# encoder.net
KiCad netlist of a schematic drawn in EAGLE
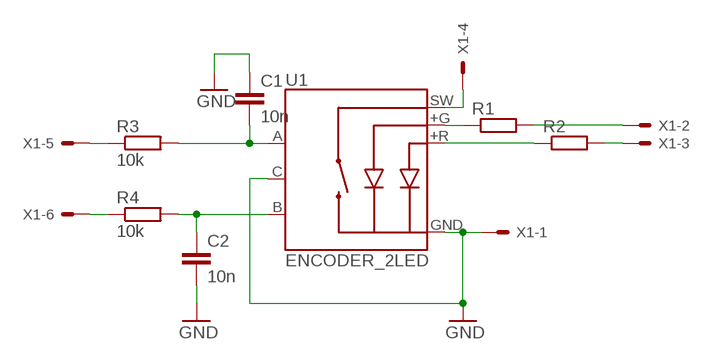
[diagram p0: schematic, sheet 1]

(export (version "E")
  (design (tool "Eeschema 10.0.6"))
  (components
    (comp (ref "C1")
      (value "10n")
      (footprint "eagle-import:C025-024X044")
      (libsource (lib "eagle-import") (part "C-EU025-024X044"))
    )
    (comp (ref "C2")
      (value "10n")
      (footprint "eagle-import:C025-024X044")
      (libsource (lib "eagle-import") (part "C-EU025-024X044"))
    )
    (comp (ref "R1")
      (value "R-EU_R0603")
      (footprint "eagle-import:R0603")
      (libsource (lib "eagle-import") (part "R-EU_R0603"))
    )
    (comp (ref "R2")
      (value "R-EU_R0603")
      (footprint "eagle-import:R0603")
      (libsource (lib "eagle-import") (part "R-EU_R0603"))
    )
    (comp (ref "R3")
      (value "10k")
      (footprint "eagle-import:R0603")
      (libsource (lib "eagle-import") (part "R-EU_R0603"))
    )
    (comp (ref "R4")
      (value "10k")
      (footprint "eagle-import:R0603")
      (libsource (lib "eagle-import") (part "R-EU_R0603"))
    )
    (comp (ref "U1")
      (value "ENCODER_2LED")
      (footprint "eagle-import:ENCODER_LED_2")
      (libsource (lib "eagle-import") (part "ENCODER_2LED"))
    )
    (comp (ref "X1")
      (value "22-23-2061")
      (footprint "eagle-import:22-23-2061")
      (fields (field (name "MF") "MOLEX"))
      (libsource (lib "eagle-import") (part "22-23-2061"))
    )
  )
  (nets
    (net (code "1") (name "GND") (class "Default")
      (node (ref "C1") (pin "1") (pinfunction "1_1") (pintype "passive"))
      (node (ref "C2") (pin "2") (pinfunction "2_2") (pintype "passive"))
      (node (ref "U1") (pin "C") (pinfunction "C_C") (pintype "bidirectional"))
      (node (ref "U1") (pin "GND") (pinfunction "-_GND") (pintype "passive"))
      (node (ref "X1") (pin "1") (pinfunction "S_1") (pintype "passive"))
    )
    (net (code "2") (name "Net-(C1-Pad2)") (class "Default")
      (node (ref "C1") (pin "2") (pinfunction "2_2") (pintype "passive"))
      (node (ref "R3") (pin "2") (pinfunction "2_2") (pintype "passive"))
      (node (ref "U1") (pin "A") (pinfunction "A_A") (pintype "bidirectional"))
    )
    (net (code "3") (name "Net-(C2-Pad1)") (class "Default")
      (node (ref "C2") (pin "1") (pinfunction "1_1") (pintype "passive"))
      (node (ref "R4") (pin "2") (pinfunction "2_2") (pintype "passive"))
      (node (ref "U1") (pin "B") (pinfunction "B_B") (pintype "bidirectional"))
    )
    (net (code "4") (name "Net-(R1-Pad1)") (class "Default")
      (node (ref "R1") (pin "1") (pinfunction "1_1") (pintype "passive"))
      (node (ref "U1") (pin "+G") (pinfunction "+G_+G") (pintype "passive"))
    )
    (net (code "5") (name "Net-(R2-Pad1)") (class "Default")
      (node (ref "R2") (pin "1") (pinfunction "1_1") (pintype "passive"))
      (node (ref "U1") (pin "+R") (pinfunction "+R_+R") (pintype "passive"))
    )
    (net (code "6") (name "Net-(X1B-S)") (class "Default")
      (node (ref "R1") (pin "2") (pinfunction "2_2") (pintype "passive"))
      (node (ref "X1") (pin "2") (pinfunction "S_2") (pintype "passive"))
    )
    (net (code "7") (name "Net-(X1C-S)") (class "Default")
      (node (ref "R2") (pin "2") (pinfunction "2_2") (pintype "passive"))
      (node (ref "X1") (pin "3") (pinfunction "S_3") (pintype "passive"))
    )
    (net (code "8") (name "Net-(X1D-S)") (class "Default")
      (node (ref "U1") (pin "SW") (pinfunction "SW_SW") (pintype "passive"))
      (node (ref "X1") (pin "4") (pinfunction "S_4") (pintype "passive"))
    )
    (net (code "9") (name "Net-(X1E-S)") (class "Default")
      (node (ref "R3") (pin "1") (pinfunction "1_1") (pintype "passive"))
      (node (ref "X1") (pin "5") (pinfunction "S_5") (pintype "passive"))
    )
    (net (code "10") (name "Net-(X1F-S)") (class "Default")
      (node (ref "R4") (pin "1") (pinfunction "1_1") (pintype "passive"))
      (node (ref "X1") (pin "6") (pinfunction "S_6") (pintype "passive"))
    )
  )
)
